# ledboard.net
KiCad netlist of a schematic drawn in EAGLE
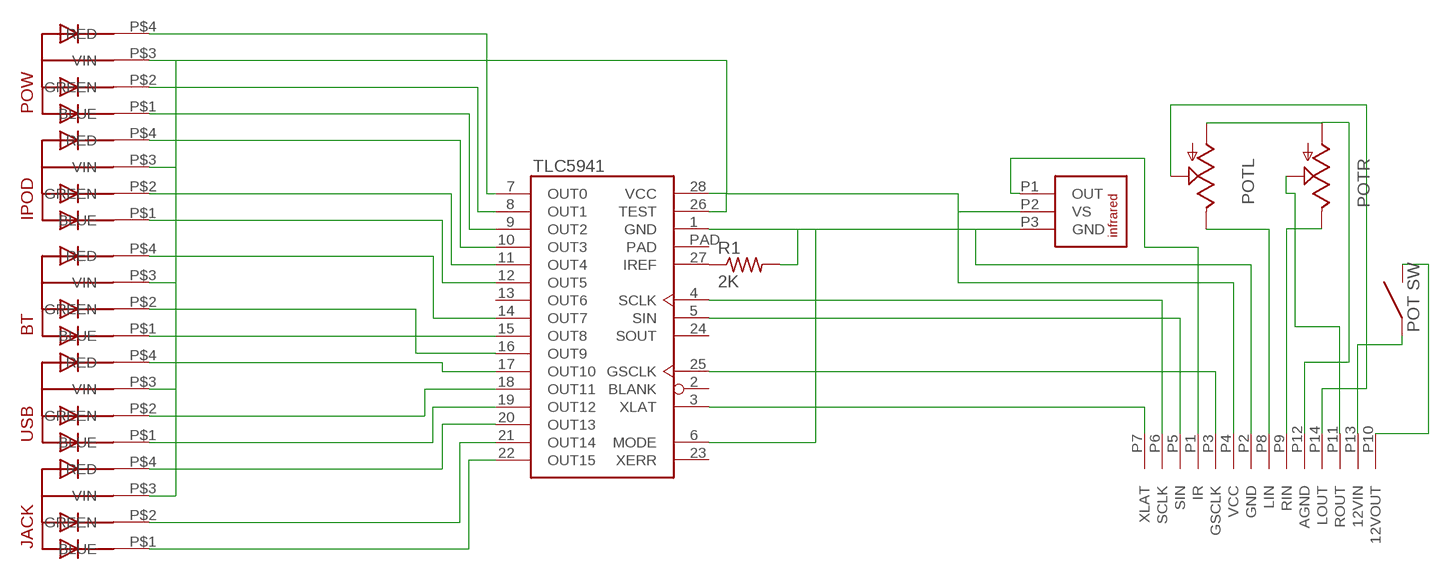
[diagram p0: schematic, sheet 1]

(export (version "E")
  (design (tool "Eeschema 10.0.6"))
  (components
    (comp (ref "BT")
      (value "5MMRGBLEDBENT")
      (footprint "eagle-import:BENTLED")
      (libsource (lib "eagle-import") (part "5MMRGBLEDBENT"))
    )
    (comp (ref "IPOD")
      (value "5MMRGBLEDBENT")
      (footprint "eagle-import:BENTLED")
      (libsource (lib "eagle-import") (part "5MMRGBLEDBENT"))
    )
    (comp (ref "IR")
      (value "TSOP323")
      (footprint "eagle-import:TSOP323")
      (libsource (lib "eagle-import") (part "TSOP323"))
    )
    (comp (ref "JACK")
      (value "5MMRGBLEDBENT")
      (footprint "eagle-import:BENTLED")
      (libsource (lib "eagle-import") (part "5MMRGBLEDBENT"))
    )
    (comp (ref "POT")
      (value "ALPS_RK0971221Z0N")
      (footprint "eagle-import:ALPS_RK0971221Z0X")
      (libsource (lib "eagle-import") (part "ALPS_RK0971221Z0N"))
    )
    (comp (ref "POW")
      (value "5MMRGBLEDBENT")
      (footprint "eagle-import:BENTLED")
      (libsource (lib "eagle-import") (part "5MMRGBLEDBENT"))
    )
    (comp (ref "R1")
      (value "2K")
      (footprint "eagle-import:0207_7")
      (libsource (lib "eagle-import") (part "R-US_0207/7"))
    )
    (comp (ref "U$1")
      (value "TLC5941")
      (footprint "eagle-import:HTSSOP28_POWERPAD")
      (libsource (lib "eagle-import") (part "TLC5941"))
    )
    (comp (ref "U$3")
      (value "CONNECTOR")
      (footprint "eagle-import:CON")
      (libsource (lib "eagle-import") (part "CONNECTOR"))
    )
    (comp (ref "USB")
      (value "5MMRGBLEDBENT")
      (footprint "eagle-import:BENTLED")
      (libsource (lib "eagle-import") (part "5MMRGBLEDBENT"))
    )
  )
  (nets
    (net (code "1") (name "Net-(BT-BLUE)") (class "Default")
      (node (ref "BT") (pin "P$1") (pinfunction "BLUE_P$1") (pintype "bidirectional"))
      (node (ref "U$1") (pin "15") (pinfunction "OUT8_15") (pintype "output"))
    )
    (net (code "2") (name "Net-(BT-GREEN)") (class "Default")
      (node (ref "BT") (pin "P$2") (pinfunction "GREEN_P$2") (pintype "bidirectional"))
      (node (ref "U$1") (pin "16") (pinfunction "OUT9_16") (pintype "output"))
    )
    (net (code "3") (name "Net-(BT-RED)") (class "Default")
      (node (ref "BT") (pin "P$4") (pinfunction "RED_P$4") (pintype "bidirectional"))
      (node (ref "U$1") (pin "14") (pinfunction "OUT7_14") (pintype "output"))
    )
    (net (code "4") (name "Net-(BT-VIN)") (class "Default")
      (node (ref "BT") (pin "P$3") (pinfunction "VIN_P$3") (pintype "bidirectional"))
      (node (ref "IPOD") (pin "P$3") (pinfunction "VIN_P$3") (pintype "bidirectional"))
      (node (ref "IR") (pin "P2") (pinfunction "VS_P2") (pintype "bidirectional"))
      (node (ref "JACK") (pin "P$3") (pinfunction "VIN_P$3") (pintype "bidirectional"))
      (node (ref "POW") (pin "P$3") (pinfunction "VIN_P$3") (pintype "bidirectional"))
      (node (ref "U$1") (pin "26") (pinfunction "TEST_26") (pintype "bidirectional"))
      (node (ref "U$1") (pin "28") (pinfunction "VCC_28") (pintype "power_in"))
      (node (ref "U$3") (pin "P4") (pinfunction "VCC_P4") (pintype "bidirectional"))
      (node (ref "USB") (pin "P$3") (pinfunction "VIN_P$3") (pintype "bidirectional"))
    )
    (net (code "5") (name "Net-(IPOD-BLUE)") (class "Default")
      (node (ref "IPOD") (pin "P$1") (pinfunction "BLUE_P$1") (pintype "bidirectional"))
      (node (ref "U$1") (pin "12") (pinfunction "OUT5_12") (pintype "output"))
    )
    (net (code "6") (name "Net-(IPOD-GREEN)") (class "Default")
      (node (ref "IPOD") (pin "P$2") (pinfunction "GREEN_P$2") (pintype "bidirectional"))
      (node (ref "U$1") (pin "11") (pinfunction "OUT4_11") (pintype "output"))
    )
    (net (code "7") (name "Net-(IPOD-RED)") (class "Default")
      (node (ref "IPOD") (pin "P$4") (pinfunction "RED_P$4") (pintype "bidirectional"))
      (node (ref "U$1") (pin "10") (pinfunction "OUT3_10") (pintype "output"))
    )
    (net (code "8") (name "Net-(IR-GND)") (class "Default")
      (node (ref "IR") (pin "P3") (pinfunction "GND_P3") (pintype "bidirectional"))
      (node (ref "R1") (pin "2") (pinfunction "2_2") (pintype "passive"))
      (node (ref "U$1") (pin "1") (pinfunction "GND_1") (pintype "power_in"))
      (node (ref "U$1") (pin "6") (pinfunction "MODE_6") (pintype "bidirectional"))
      (node (ref "U$3") (pin "P2") (pinfunction "GND_P2") (pintype "bidirectional"))
    )
    (net (code "9") (name "Net-(IR-OUT)") (class "Default")
      (node (ref "IR") (pin "P1") (pinfunction "OUT_P1") (pintype "bidirectional"))
      (node (ref "U$3") (pin "P1") (pinfunction "IR_P1") (pintype "bidirectional"))
    )
    (net (code "10") (name "Net-(JACK-BLUE)") (class "Default")
      (node (ref "JACK") (pin "P$1") (pinfunction "BLUE_P$1") (pintype "bidirectional"))
      (node (ref "U$1") (pin "22") (pinfunction "OUT15_22") (pintype "output"))
    )
    (net (code "11") (name "Net-(JACK-GREEN)") (class "Default")
      (node (ref "JACK") (pin "P$2") (pinfunction "GREEN_P$2") (pintype "bidirectional"))
      (node (ref "U$1") (pin "21") (pinfunction "OUT14_21") (pintype "output"))
    )
    (net (code "12") (name "Net-(JACK-RED)") (class "Default")
      (node (ref "JACK") (pin "P$4") (pinfunction "RED_P$4") (pintype "bidirectional"))
      (node (ref "U$1") (pin "20") (pinfunction "OUT13_20") (pintype "output"))
    )
    (net (code "13") (name "Net-(POTB-1)") (class "Default")
      (node (ref "POT") (pin "G1") (pinfunction "1_G1") (pintype "passive"))
      (node (ref "POT") (pin "G2") (pinfunction "1_G2") (pintype "passive"))
      (node (ref "U$3") (pin "P12") (pinfunction "AGND_P12") (pintype "bidirectional"))
    )
    (net (code "14") (name "Net-(POTB-2)") (class "Default")
      (node (ref "POT") (pin "O1") (pinfunction "2_O1") (pintype "passive"))
      (node (ref "U$3") (pin "P14") (pinfunction "LOUT_P14") (pintype "bidirectional"))
    )
    (net (code "15") (name "Net-(POTB-3)") (class "Default")
      (node (ref "POT") (pin "I1") (pinfunction "3_I1") (pintype "passive"))
      (node (ref "U$3") (pin "P8") (pinfunction "LIN_P8") (pintype "bidirectional"))
    )
    (net (code "16") (name "Net-(POTC-2)") (class "Default")
      (node (ref "POT") (pin "O2") (pinfunction "2_O2") (pintype "passive"))
      (node (ref "U$3") (pin "P11") (pinfunction "ROUT_P11") (pintype "bidirectional"))
    )
    (net (code "17") (name "Net-(POTC-3)") (class "Default")
      (node (ref "POT") (pin "I2") (pinfunction "3_I2") (pintype "passive"))
      (node (ref "U$3") (pin "P9") (pinfunction "RIN_P9") (pintype "bidirectional"))
    )
    (net (code "18") (name "Net-(POW-BLUE)") (class "Default")
      (node (ref "POW") (pin "P$1") (pinfunction "BLUE_P$1") (pintype "bidirectional"))
      (node (ref "U$1") (pin "9") (pinfunction "OUT2_9") (pintype "output"))
    )
    (net (code "19") (name "Net-(POW-GREEN)") (class "Default")
      (node (ref "POW") (pin "P$2") (pinfunction "GREEN_P$2") (pintype "bidirectional"))
      (node (ref "U$1") (pin "8") (pinfunction "OUT1_8") (pintype "output"))
    )
    (net (code "20") (name "Net-(POW-RED)") (class "Default")
      (node (ref "POW") (pin "P$4") (pinfunction "RED_P$4") (pintype "bidirectional"))
      (node (ref "U$1") (pin "7") (pinfunction "OUT0_7") (pintype "output"))
    )
    (net (code "21") (name "Net-(U$1-GSCLK)") (class "Default")
      (node (ref "U$1") (pin "25") (pinfunction "GSCLK_25") (pintype "input"))
      (node (ref "U$3") (pin "P3") (pinfunction "GSCLK_P3") (pintype "bidirectional"))
    )
    (net (code "22") (name "Net-(U$1-IREF)") (class "Default")
      (node (ref "R1") (pin "1") (pinfunction "1_1") (pintype "passive"))
      (node (ref "U$1") (pin "27") (pinfunction "IREF_27") (pintype "input"))
    )
    (net (code "23") (name "Net-(U$1-OUT10)") (class "Default")
      (node (ref "U$1") (pin "17") (pinfunction "OUT10_17") (pintype "output"))
      (node (ref "USB") (pin "P$4") (pinfunction "RED_P$4") (pintype "bidirectional"))
    )
    (net (code "24") (name "Net-(U$1-OUT11)") (class "Default")
      (node (ref "U$1") (pin "18") (pinfunction "OUT11_18") (pintype "output"))
      (node (ref "USB") (pin "P$2") (pinfunction "GREEN_P$2") (pintype "bidirectional"))
    )
    (net (code "25") (name "Net-(U$1-OUT12)") (class "Default")
      (node (ref "U$1") (pin "19") (pinfunction "OUT12_19") (pintype "output"))
      (node (ref "USB") (pin "P$1") (pinfunction "BLUE_P$1") (pintype "bidirectional"))
    )
    (net (code "26") (name "Net-(U$1-SCLK)") (class "Default")
      (node (ref "U$1") (pin "4") (pinfunction "SCLK_4") (pintype "input"))
      (node (ref "U$3") (pin "P6") (pinfunction "SCLK_P6") (pintype "bidirectional"))
    )
    (net (code "27") (name "Net-(U$1-SIN)") (class "Default")
      (node (ref "U$1") (pin "5") (pinfunction "SIN_5") (pintype "input"))
      (node (ref "U$3") (pin "P5") (pinfunction "SIN_P5") (pintype "bidirectional"))
    )
    (net (code "28") (name "Net-(U$1-XLAT)") (class "Default")
      (node (ref "U$1") (pin "3") (pinfunction "XLAT_3") (pintype "input"))
      (node (ref "U$3") (pin "P7") (pinfunction "XLAT_P7") (pintype "bidirectional"))
    )
    (net (code "29") (name "Net-(U$3-12VIN)") (class "Default")
      (node (ref "POT") (pin "S1") (pinfunction "S1_S1") (pintype "power_in"))
      (node (ref "U$3") (pin "P13") (pinfunction "12VIN_P13") (pintype "bidirectional"))
    )
    (net (code "30") (name "Net-(U$3-12VOUT)") (class "Default")
      (node (ref "POT") (pin "S2") (pinfunction "S2_S2") (pintype "power_in"))
      (node (ref "U$3") (pin "P10") (pinfunction "12VOUT_P10") (pintype "bidirectional"))
    )
    (net (code "31") (name "unconnected-(U$1-BLANK-Pad2)") (class "Default")
      (node (ref "U$1") (pin "2") (pinfunction "BLANK_2") (pintype "input"))
    )
    (net (code "32") (name "unconnected-(U$1-OUT6-Pad13)") (class "Default")
      (node (ref "U$1") (pin "13") (pinfunction "OUT6_13") (pintype "output"))
    )
    (net (code "33") (name "unconnected-(U$1-PadPAD)") (class "Default")
      (node (ref "U$1") (pin "PAD") (pinfunction "PAD_PAD") (pintype "bidirectional"))
    )
    (net (code "34") (name "unconnected-(U$1-SOUT-Pad24)") (class "Default")
      (node (ref "U$1") (pin "24") (pinfunction "SOUT_24") (pintype "output"))
    )
    (net (code "35") (name "unconnected-(U$1-XERR-Pad23)") (class "Default")
      (node (ref "U$1") (pin "23") (pinfunction "XERR_23") (pintype "output"))
    )
  )
)
